# Noise_Diode_power_supply.net
KiCad netlist of a schematic drawn in Altium Designer
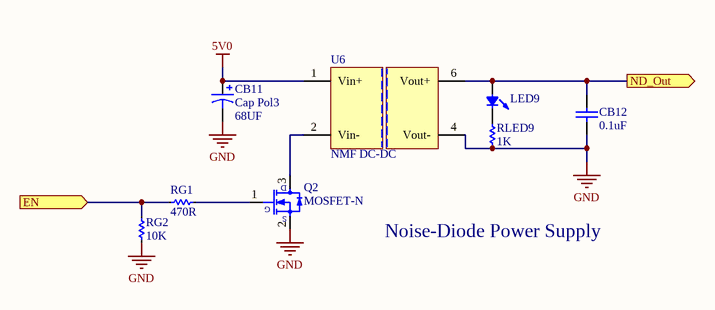
[diagram p0: Noise Diode power supply.SchDoc]

(export (version "E")
  (design (tool "Eeschema 10.0.6"))
  (components
    (comp (ref "CB11")
      (value "Cap Pol3")
      (footprint "V")
      (description "KEMET T520 KO-CAP  Polymer SMT Tantalum")
      (fields (field (name "ALTIUM_VALUE") "68UF") (field (name "VOLTAGE") "10V"))
      (libsource (lib "Miscellaneous Devices") (part "Cap Pol3"))
    )
    (comp (ref "CB12")
      (value "0.1uF")
      (footprint "0603C")
      (description "Capacitor (Semiconductor SIM Model)")
      (fields (field (name "Comment") "Cap Semi") (field (name "PUBLISHER") "Altium Limited"))
      (libsource (lib "Miscellaneous Devices") (part "Cap Semi"))
    )
    (comp (ref "LED9")
      (value "LED0")
      (footprint "T1 LED")
      (description "T 1 3/4 LED")
      (fields (field (name "PUBLISHER") "Altium Limited"))
      (libsource (lib "Miscellaneous Devices") (part "LED0"))
    )
    (comp (ref "Q2")
      (value "MOSFET-N")
      (footprint "SOT23-3N")
      (description "N-Channel MOSFET")
      (fields (field (name "PUBLISHER") "Altium Limited"))
      (libsource (lib "Miscellaneous Devices") (part "MOSFET-N"))
    )
    (comp (ref "RG1")
      (value "470R")
      (footprint "0603R")
      (description "Semiconductor Resistor")
      (fields (field (name "Comment") "Res Semi Small") (field (name "PUBLISHER") "Altium Limited"))
      (libsource (lib "Miscellaneous Devices") (part "Res Semi Small"))
    )
    (comp (ref "RG2")
      (value "10K")
      (footprint "0603R")
      (description "Semiconductor Resistor")
      (fields (field (name "Comment") "Res Semi Small") (field (name "PUBLISHER") "Altium Limited"))
      (libsource (lib "Miscellaneous Devices") (part "Res Semi Small"))
    )
    (comp (ref "RLED9")
      (value "1K")
      (footprint "0603R")
      (description "Semiconductor Resistor")
      (fields (field (name "Comment") "Res Semi Small") (field (name "PUBLISHER") "Altium Limited"))
      (libsource (lib "Miscellaneous Devices") (part "Res Semi Small"))
    )
    (comp (ref "U6")
      (value "NMF DC-DC")
      (footprint "SIL-6(A1)")
      (description "Murata NMF DC-DC - 1W, Single output")
      (libsource (lib "Unsorted") (part "Murata NMF DC-DC"))
    )
  )
  (nets
    (net (code "1") (name "/EN") (class "Default")
      (node (ref "RG1") (pin "1") (pinfunction "1_1") (pintype "passive"))
      (node (ref "RG2") (pin "2") (pinfunction "2_2") (pintype "passive"))
    )
    (net (code "2") (name "/ND_Out") (class "Default")
      (node (ref "CB12") (pin "2") (pinfunction "2_2") (pintype "passive"))
      (node (ref "LED9") (pin "1") (pinfunction "1_1") (pintype "passive"))
      (node (ref "U6") (pin "6") (pinfunction "Vout+_6") (pintype "power_in"))
    )
    (net (code "3") (name "5V0") (class "Default")
      (node (ref "CB11") (pin "1") (pinfunction "1_1") (pintype "passive"))
      (node (ref "U6") (pin "1") (pinfunction "Vin+_1") (pintype "power_in"))
    )
    (net (code "4") (name "GND") (class "Default")
      (node (ref "CB11") (pin "2") (pinfunction "2_2") (pintype "passive"))
      (node (ref "CB12") (pin "1") (pinfunction "1_1") (pintype "passive"))
      (node (ref "Q2") (pin "2") (pinfunction "S_2") (pintype "passive"))
      (node (ref "RG2") (pin "1") (pinfunction "1_1") (pintype "passive"))
      (node (ref "RLED9") (pin "2") (pinfunction "2_2") (pintype "passive"))
      (node (ref "U6") (pin "4") (pinfunction "Vout-_4") (pintype "power_in"))
    )
    (net (code "5") (name "Net-(LED9-Pad2)") (class "Default")
      (node (ref "LED9") (pin "2") (pinfunction "2_2") (pintype "passive"))
      (node (ref "RLED9") (pin "1") (pinfunction "1_1") (pintype "passive"))
    )
    (net (code "6") (name "Net-(Q2-D)") (class "Default")
      (node (ref "Q2") (pin "3") (pinfunction "D_3") (pintype "passive"))
      (node (ref "U6") (pin "2") (pinfunction "Vin-_2") (pintype "power_in"))
    )
    (net (code "7") (name "Net-(Q2-G)") (class "Default")
      (node (ref "Q2") (pin "1") (pinfunction "G_1") (pintype "passive"))
      (node (ref "RG1") (pin "2") (pinfunction "2_2") (pintype "passive"))
    )
  )
)
